# XBee.net
KiCad netlist of a schematic drawn in EAGLE
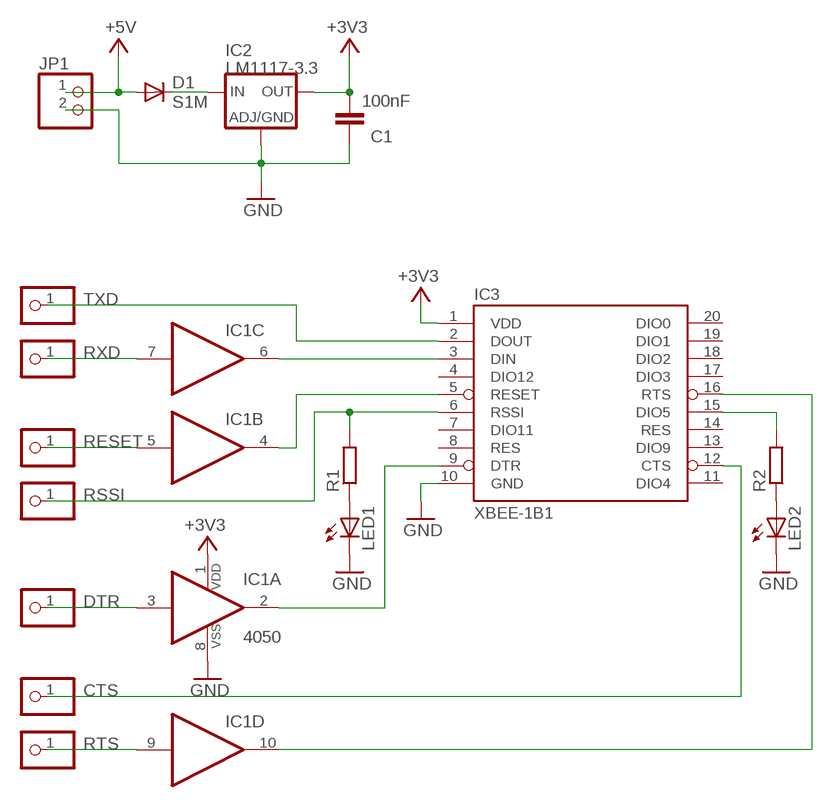
[diagram p0: schematic, sheet 1]

(export (version "E")
  (design (tool "Eeschema 10.0.6"))
  (components
    (comp (ref "C1")
      (value "100nF")
      (footprint "eagle-import:C0805K")
      (libsource (lib "eagle-import") (part "C-EUC0805K"))
    )
    (comp (ref "D1")
      (value "S1M")
      (footprint "eagle-import:DO-214AC")
      (libsource (lib "eagle-import") (part "S1M"))
    )
    (comp (ref "IC1")
      (value "4050")
      (footprint "eagle-import:SO16")
      (libsource (lib "eagle-import") (part "4050D"))
    )
    (comp (ref "IC2")
      (value "LM1117-3.3")
      (footprint "eagle-import:SOT223")
      (libsource (lib "eagle-import") (part "LM1117S"))
    )
    (comp (ref "IC3")
      (value "XBEE-1B1")
      (footprint "eagle-import:XBEE-1")
      (libsource (lib "eagle-import") (part "XBEE-1B1"))
    )
    (comp (ref "JP1")
      (value "PINHD-1X2")
      (footprint "eagle-import:1X02")
      (libsource (lib "eagle-import") (part "PINHD-1X2"))
    )
    (comp (ref "JP2")
      (value "TXD")
      (footprint "eagle-import:1X01")
      (libsource (lib "eagle-import") (part "PINHD-1X1"))
    )
    (comp (ref "JP3")
      (value "RXD")
      (footprint "eagle-import:1X01")
      (libsource (lib "eagle-import") (part "PINHD-1X1"))
    )
    (comp (ref "JP4")
      (value "RST")
      (footprint "eagle-import:1X01")
      (libsource (lib "eagle-import") (part "PINHD-1X1"))
    )
    (comp (ref "JP5")
      (value "RSSI")
      (footprint "eagle-import:1X01")
      (libsource (lib "eagle-import") (part "PINHD-1X1"))
    )
    (comp (ref "JP6")
      (value "DTR")
      (footprint "eagle-import:1X01")
      (libsource (lib "eagle-import") (part "PINHD-1X1"))
    )
    (comp (ref "JP7")
      (value "CTS")
      (footprint "eagle-import:1X01")
      (libsource (lib "eagle-import") (part "PINHD-1X1"))
    )
    (comp (ref "JP8")
      (value "RTS")
      (footprint "eagle-import:1X01")
      (libsource (lib "eagle-import") (part "PINHD-1X1"))
    )
    (comp (ref "LED1")
      (value "LED3MM")
      (footprint "eagle-import:LED3MM")
      (libsource (lib "eagle-import") (part "LED3MM"))
    )
    (comp (ref "LED2")
      (value "LED3MM")
      (footprint "eagle-import:LED3MM")
      (libsource (lib "eagle-import") (part "LED3MM"))
    )
    (comp (ref "R1")
      (value "R-EU_R0805")
      (footprint "eagle-import:R0805")
      (libsource (lib "eagle-import") (part "R-EU_R0805"))
    )
    (comp (ref "R2")
      (value "R-EU_R0805")
      (footprint "eagle-import:R0805")
      (libsource (lib "eagle-import") (part "R-EU_R0805"))
    )
  )
  (nets
    (net (code "1") (name "+3V3") (class "Default")
      (node (ref "C1") (pin "2") (pinfunction "2_2") (pintype "passive"))
      (node (ref "IC1") (pin "1") (pinfunction "VDD_1") (pintype "power_in"))
      (node (ref "IC2") (pin "2") (pinfunction "OUT_2") (pintype "passive"))
      (node (ref "IC2") (pin "4") (pinfunction "OUT_4") (pintype "passive"))
      (node (ref "IC3") (pin "1") (pinfunction "VDD_1") (pintype "power_in"))
    )
    (net (code "2") (name "+5V") (class "Default")
      (node (ref "D1") (pin "A") (pinfunction "A_A") (pintype "passive"))
      (node (ref "JP1") (pin "1") (pinfunction "1_1") (pintype "passive"))
    )
    (net (code "3") (name "/CTS") (class "Default")
      (node (ref "IC3") (pin "12") (pinfunction "CTS_12") (pintype "output"))
      (node (ref "JP7") (pin "1") (pinfunction "1_1") (pintype "passive"))
    )
    (net (code "4") (name "/DTR") (class "Default")
      (node (ref "IC1") (pin "3") (pinfunction "I_3") (pintype "input"))
      (node (ref "JP6") (pin "1") (pinfunction "1_1") (pintype "passive"))
    )
    (net (code "5") (name "/RESET") (class "Default")
      (node (ref "IC1") (pin "5") (pinfunction "I_5") (pintype "input"))
      (node (ref "JP4") (pin "1") (pinfunction "1_1") (pintype "passive"))
    )
    (net (code "6") (name "/RSSI") (class "Default")
      (node (ref "IC3") (pin "6") (pinfunction "RSSI_6") (pintype "bidirectional"))
      (node (ref "JP5") (pin "1") (pinfunction "1_1") (pintype "passive"))
      (node (ref "R1") (pin "2") (pinfunction "2_2") (pintype "passive"))
    )
    (net (code "7") (name "/RTS") (class "Default")
      (node (ref "IC1") (pin "9") (pinfunction "I_9") (pintype "input"))
      (node (ref "JP8") (pin "1") (pinfunction "1_1") (pintype "passive"))
    )
    (net (code "8") (name "/RXD") (class "Default")
      (node (ref "IC1") (pin "7") (pinfunction "I_7") (pintype "input"))
      (node (ref "JP3") (pin "1") (pinfunction "1_1") (pintype "passive"))
    )
    (net (code "9") (name "/TXD") (class "Default")
      (node (ref "IC3") (pin "2") (pinfunction "DOUT_2") (pintype "output"))
      (node (ref "JP2") (pin "1") (pinfunction "1_1") (pintype "passive"))
    )
    (net (code "10") (name "GND") (class "Default")
      (node (ref "C1") (pin "1") (pinfunction "1_1") (pintype "passive"))
      (node (ref "IC1") (pin "8") (pinfunction "VSS_8") (pintype "power_in"))
      (node (ref "IC2") (pin "1") (pinfunction "ADJ_1") (pintype "input"))
      (node (ref "IC3") (pin "10") (pinfunction "GND_10") (pintype "power_in"))
      (node (ref "JP1") (pin "2") (pinfunction "2_2") (pintype "passive"))
      (node (ref "LED1") (pin "K") (pinfunction "C_K") (pintype "passive"))
      (node (ref "LED2") (pin "K") (pinfunction "C_K") (pintype "passive"))
    )
    (net (code "11") (name "Net-(IC1A-O)") (class "Default")
      (node (ref "IC1") (pin "2") (pinfunction "O_2") (pintype "output"))
      (node (ref "IC3") (pin "9") (pinfunction "DTR_9") (pintype "bidirectional"))
    )
    (net (code "12") (name "Net-(IC1B-O)") (class "Default")
      (node (ref "IC1") (pin "4") (pinfunction "O_4") (pintype "output"))
      (node (ref "IC3") (pin "5") (pinfunction "RESET_5") (pintype "input"))
    )
    (net (code "13") (name "Net-(IC1C-O)") (class "Default")
      (node (ref "IC1") (pin "6") (pinfunction "O_6") (pintype "output"))
      (node (ref "IC3") (pin "3") (pinfunction "DIN_3") (pintype "input"))
    )
    (net (code "14") (name "Net-(IC1D-O)") (class "Default")
      (node (ref "IC1") (pin "10") (pinfunction "O_10") (pintype "output"))
      (node (ref "IC3") (pin "16") (pinfunction "RTS_16") (pintype "input"))
    )
    (net (code "15") (name "Net-(IC2-IN)") (class "Default")
      (node (ref "D1") (pin "C") (pinfunction "C_C") (pintype "passive"))
      (node (ref "IC2") (pin "3") (pinfunction "IN_3") (pintype "input"))
    )
    (net (code "16") (name "Net-(IC3-DIO5)") (class "Default")
      (node (ref "IC3") (pin "15") (pinfunction "DIO5_15") (pintype "bidirectional"))
      (node (ref "R2") (pin "2") (pinfunction "2_2") (pintype "passive"))
    )
    (net (code "17") (name "Net-(LED1-PadA)") (class "Default")
      (node (ref "LED1") (pin "A") (pinfunction "A_A") (pintype "passive"))
      (node (ref "R1") (pin "1") (pinfunction "1_1") (pintype "passive"))
    )
    (net (code "18") (name "Net-(LED2-PadA)") (class "Default")
      (node (ref "LED2") (pin "A") (pinfunction "A_A") (pintype "passive"))
      (node (ref "R2") (pin "1") (pinfunction "1_1") (pintype "passive"))
    )
    (net (code "19") (name "unconnected-(IC3-DIO0-Pad20)") (class "Default")
      (node (ref "IC3") (pin "20") (pinfunction "DIO0_20") (pintype "bidirectional"))
    )
    (net (code "20") (name "unconnected-(IC3-DIO1-Pad19)") (class "Default")
      (node (ref "IC3") (pin "19") (pinfunction "DIO1_19") (pintype "bidirectional"))
    )
    (net (code "21") (name "unconnected-(IC3-DIO2-Pad18)") (class "Default")
      (node (ref "IC3") (pin "18") (pinfunction "DIO2_18") (pintype "bidirectional"))
    )
    (net (code "22") (name "unconnected-(IC3-DIO3-Pad17)") (class "Default")
      (node (ref "IC3") (pin "17") (pinfunction "DIO3_17") (pintype "bidirectional"))
    )
    (net (code "23") (name "unconnected-(IC3-DIO4-Pad11)") (class "Default")
      (node (ref "IC3") (pin "11") (pinfunction "DIO4_11") (pintype "bidirectional"))
    )
    (net (code "24") (name "unconnected-(IC3-DIO9-Pad13)") (class "Default")
      (node (ref "IC3") (pin "13") (pinfunction "DIO9_13") (pintype "bidirectional"))
    )
    (net (code "25") (name "unconnected-(IC3-DIO11-Pad7)") (class "Default")
      (node (ref "IC3") (pin "7") (pinfunction "DIO11_7") (pintype "bidirectional"))
    )
    (net (code "26") (name "unconnected-(IC3-DIO12-Pad4)") (class "Default")
      (node (ref "IC3") (pin "4") (pinfunction "DIO12_4") (pintype "bidirectional"))
    )
    (net (code "27") (name "unconnected-(IC3-RES-Pad8)") (class "Default")
      (node (ref "IC3") (pin "8") (pinfunction "RES_8") (pintype "bidirectional"))
    )
    (net (code "28") (name "unconnected-(IC3-RES-Pad14)") (class "Default")
      (node (ref "IC3") (pin "14") (pinfunction "RES_14") (pintype "bidirectional"))
    )
  )
)
